# Relay.net
KiCad netlist of a schematic drawn in Altium Designer
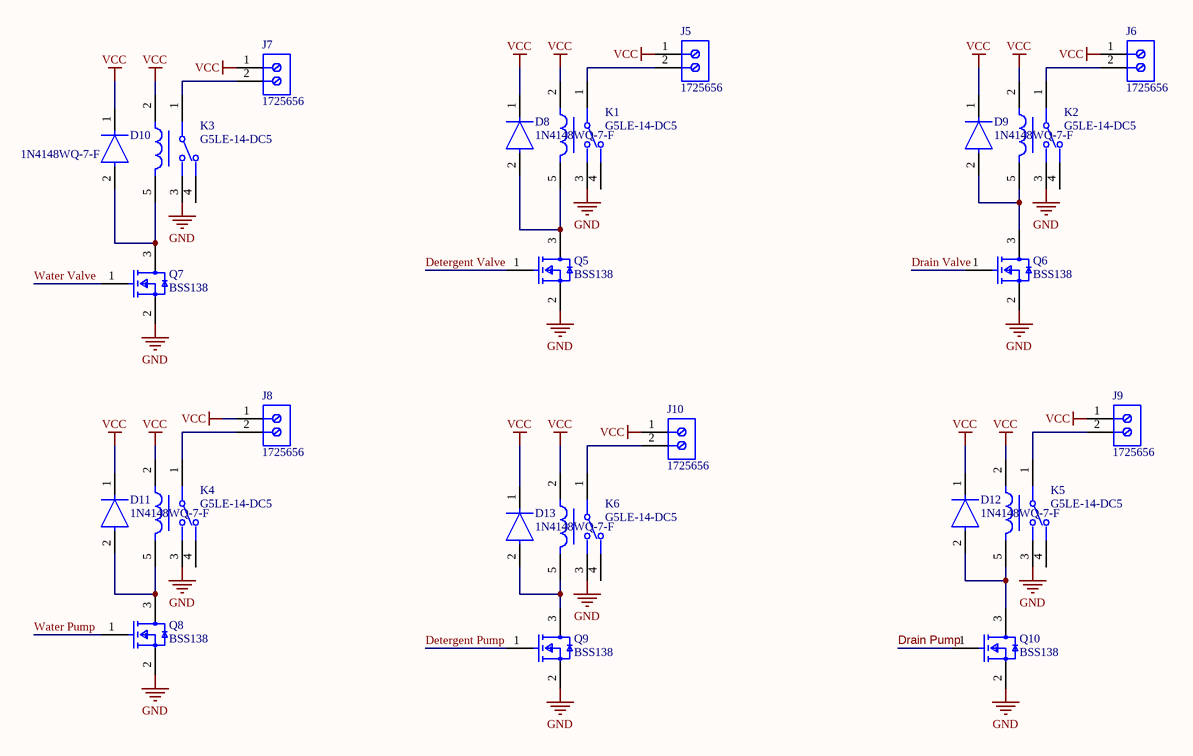
[diagram p0: Relay.SchDoc]

(export (version "E")
  (design (tool "Eeschema 10.0.6"))
  (components
    (comp (ref "D8")
      (value "1N4148WQ-7-F")
      (footprint "FP-SOD123-MFG")
      (description "DIODE GEN PURP 100V 300MA SOD123")
      (fields
        (field (name "MANUFACTURER") "Diodes Inc.")
        (field (name "OCTOPART") "https://octopart.com/1n4148wq-7-f-diodes+inc.-34965875")
      )
      (libsource (lib "Altium Content Vault") (part "d7152d700b627762746794eb795d46e"))
    )
    (comp (ref "D9")
      (value "1N4148WQ-7-F")
      (footprint "FP-SOD123-MFG")
      (description "DIODE GEN PURP 100V 300MA SOD123")
      (fields
        (field (name "MANUFACTURER") "Diodes Inc.")
        (field (name "OCTOPART") "https://octopart.com/1n4148wq-7-f-diodes+inc.-34965875")
      )
      (libsource (lib "Altium Content Vault") (part "d7152d700b627762746794eb795d46e"))
    )
    (comp (ref "D10")
      (value "1N4148WQ-7-F")
      (footprint "FP-SOD123-MFG")
      (description "DIODE GEN PURP 100V 300MA SOD123")
      (fields
        (field (name "MANUFACTURER") "Diodes Inc.")
        (field (name "OCTOPART") "https://octopart.com/1n4148wq-7-f-diodes+inc.-34965875")
      )
      (libsource (lib "Altium Content Vault") (part "d7152d700b627762746794eb795d46e"))
    )
    (comp (ref "D11")
      (value "1N4148WQ-7-F")
      (footprint "FP-SOD123-MFG")
      (description "DIODE GEN PURP 100V 300MA SOD123")
      (fields
        (field (name "MANUFACTURER") "Diodes Inc.")
        (field (name "OCTOPART") "https://octopart.com/1n4148wq-7-f-diodes+inc.-34965875")
      )
      (libsource (lib "Altium Content Vault") (part "d7152d700b627762746794eb795d46e"))
    )
    (comp (ref "D12")
      (value "1N4148WQ-7-F")
      (footprint "FP-SOD123-MFG")
      (description "DIODE GEN PURP 100V 300MA SOD123")
      (fields
        (field (name "MANUFACTURER") "Diodes Inc.")
        (field (name "OCTOPART") "https://octopart.com/1n4148wq-7-f-diodes+inc.-34965875")
      )
      (libsource (lib "Altium Content Vault") (part "d7152d700b627762746794eb795d46e"))
    )
    (comp (ref "D13")
      (value "1N4148WQ-7-F")
      (footprint "FP-SOD123-MFG")
      (description "DIODE GEN PURP 100V 300MA SOD123")
      (fields
        (field (name "MANUFACTURER") "Diodes Inc.")
        (field (name "OCTOPART") "https://octopart.com/1n4148wq-7-f-diodes+inc.-34965875")
      )
      (libsource (lib "Altium Content Vault") (part "d7152d700b627762746794eb795d46e"))
    )
    (comp (ref "J5")
      (value "1725656")
      (footprint "PHOE-1725656-2")
      (description "Male Header, Pitch 2.54 mm, 1 x 2 Position, Height 9 mm, Tail Length 3.5 mm")
      (fields (field (name "MANUFACTURER") "Phoenix Contact"))
      (libsource (lib "Altium Content Vault") (part "CN-1P-F-TB2"))
    )
    (comp (ref "J6")
      (value "1725656")
      (footprint "PHOE-1725656-2")
      (description "Male Header, Pitch 2.54 mm, 1 x 2 Position, Height 9 mm, Tail Length 3.5 mm")
      (fields (field (name "MANUFACTURER") "Phoenix Contact"))
      (libsource (lib "Altium Content Vault") (part "CN-1P-F-TB2"))
    )
    (comp (ref "J7")
      (value "1725656")
      (footprint "PHOE-1725656-2")
      (description "Male Header, Pitch 2.54 mm, 1 x 2 Position, Height 9 mm, Tail Length 3.5 mm")
      (fields (field (name "MANUFACTURER") "Phoenix Contact"))
      (libsource (lib "Altium Content Vault") (part "CN-1P-F-TB2"))
    )
    (comp (ref "J8")
      (value "1725656")
      (footprint "PHOE-1725656-2")
      (description "Male Header, Pitch 2.54 mm, 1 x 2 Position, Height 9 mm, Tail Length 3.5 mm")
      (fields (field (name "MANUFACTURER") "Phoenix Contact"))
      (libsource (lib "Altium Content Vault") (part "CN-1P-F-TB2"))
    )
    (comp (ref "J9")
      (value "1725656")
      (footprint "PHOE-1725656-2")
      (description "Male Header, Pitch 2.54 mm, 1 x 2 Position, Height 9 mm, Tail Length 3.5 mm")
      (fields (field (name "MANUFACTURER") "Phoenix Contact"))
      (libsource (lib "Altium Content Vault") (part "CN-1P-F-TB2"))
    )
    (comp (ref "J10")
      (value "1725656")
      (footprint "PHOE-1725656-2")
      (description "Male Header, Pitch 2.54 mm, 1 x 2 Position, Height 9 mm, Tail Length 3.5 mm")
      (fields (field (name "MANUFACTURER") "Phoenix Contact"))
      (libsource (lib "Altium Content Vault") (part "CN-1P-F-TB2"))
    )
    (comp (ref "K1")
      (value "G5LE-14-DC5")
      (footprint "FP-G5LE-14-DC5-MFG")
      (description "RELAY GEN PURPOSE SPDT 10A 5V")
      (fields
        (field (name "OCTOPART") "https://octopart.com/g5le-14-dc5-omron-28829")
        (field (name "MANUFACTURER") "Omron")
      )
      (libsource (lib "Altium Content Vault") (part "c03b8d08e5d02e70a6880f365e34168"))
    )
    (comp (ref "K2")
      (value "G5LE-14-DC5")
      (footprint "FP-G5LE-14-DC5-MFG")
      (description "RELAY GEN PURPOSE SPDT 10A 5V")
      (fields
        (field (name "OCTOPART") "https://octopart.com/g5le-14-dc5-omron-28829")
        (field (name "MANUFACTURER") "Omron")
      )
      (libsource (lib "Altium Content Vault") (part "c03b8d08e5d02e70a6880f365e34168"))
    )
    (comp (ref "K3")
      (value "G5LE-14-DC5")
      (footprint "FP-G5LE-14-DC5-MFG")
      (description "RELAY GEN PURPOSE SPDT 10A 5V")
      (fields
        (field (name "OCTOPART") "https://octopart.com/g5le-14-dc5-omron-28829")
        (field (name "MANUFACTURER") "Omron")
      )
      (libsource (lib "Altium Content Vault") (part "c03b8d08e5d02e70a6880f365e34168"))
    )
    (comp (ref "K4")
      (value "G5LE-14-DC5")
      (footprint "FP-G5LE-14-DC5-MFG")
      (description "RELAY GEN PURPOSE SPDT 10A 5V")
      (fields
        (field (name "OCTOPART") "https://octopart.com/g5le-14-dc5-omron-28829")
        (field (name "MANUFACTURER") "Omron")
      )
      (libsource (lib "Altium Content Vault") (part "c03b8d08e5d02e70a6880f365e34168"))
    )
    (comp (ref "K5")
      (value "G5LE-14-DC5")
      (footprint "FP-G5LE-14-DC5-MFG")
      (description "RELAY GEN PURPOSE SPDT 10A 5V")
      (fields
        (field (name "OCTOPART") "https://octopart.com/g5le-14-dc5-omron-28829")
        (field (name "MANUFACTURER") "Omron")
      )
      (libsource (lib "Altium Content Vault") (part "c03b8d08e5d02e70a6880f365e34168"))
    )
    (comp (ref "K6")
      (value "G5LE-14-DC5")
      (footprint "FP-G5LE-14-DC5-MFG")
      (description "RELAY GEN PURPOSE SPDT 10A 5V")
      (fields
        (field (name "OCTOPART") "https://octopart.com/g5le-14-dc5-omron-28829")
        (field (name "MANUFACTURER") "Omron")
      )
      (libsource (lib "Altium Content Vault") (part "c03b8d08e5d02e70a6880f365e34168"))
    )
    (comp (ref "Q5")
      (value "BSS138")
      (footprint "FP-318-08-IPC_A")
      (description "MOSFET N-CH 50V 220MA SOT-23")
      (libsource (lib "Altium Content Vault") (part "3b9c635fedb024a5347a57b145af9cc"))
    )
    (comp (ref "Q6")
      (value "BSS138")
      (footprint "FP-318-08-IPC_A")
      (description "MOSFET N-CH 50V 220MA SOT-23")
      (libsource (lib "Altium Content Vault") (part "3b9c635fedb024a5347a57b145af9cc"))
    )
    (comp (ref "Q7")
      (value "BSS138")
      (footprint "FP-318-08-IPC_A")
      (description "MOSFET N-CH 50V 220MA SOT-23")
      (libsource (lib "Altium Content Vault") (part "3b9c635fedb024a5347a57b145af9cc"))
    )
    (comp (ref "Q8")
      (value "BSS138")
      (footprint "FP-318-08-IPC_A")
      (description "MOSFET N-CH 50V 220MA SOT-23")
      (libsource (lib "Altium Content Vault") (part "3b9c635fedb024a5347a57b145af9cc"))
    )
    (comp (ref "Q9")
      (value "BSS138")
      (footprint "FP-318-08-IPC_A")
      (description "MOSFET N-CH 50V 220MA SOT-23")
      (libsource (lib "Altium Content Vault") (part "3b9c635fedb024a5347a57b145af9cc"))
    )
    (comp (ref "Q10")
      (value "BSS138")
      (footprint "FP-318-08-IPC_A")
      (description "MOSFET N-CH 50V 220MA SOT-23")
      (libsource (lib "Altium Content Vault") (part "3b9c635fedb024a5347a57b145af9cc"))
    )
  )
  (nets
    (net (code "1") (name "/Detergent Pump") (class "Default")
      (node (ref "Q9") (pin "1") (pinfunction "G_1") (pintype "passive"))
    )
    (net (code "2") (name "/Detergent Valve") (class "Default")
      (node (ref "Q5") (pin "1") (pinfunction "G_1") (pintype "passive"))
    )
    (net (code "3") (name "/Drain Pump") (class "Default")
      (node (ref "Q10") (pin "1") (pinfunction "G_1") (pintype "passive"))
    )
    (net (code "4") (name "/Drain Valve") (class "Default")
      (node (ref "Q6") (pin "1") (pinfunction "G_1") (pintype "passive"))
    )
    (net (code "5") (name "/Water Pump") (class "Default")
      (node (ref "Q8") (pin "1") (pinfunction "G_1") (pintype "passive"))
    )
    (net (code "6") (name "/Water Valve") (class "Default")
      (node (ref "Q7") (pin "1") (pinfunction "G_1") (pintype "passive"))
    )
    (net (code "7") (name "GND") (class "Default")
      (node (ref "K1") (pin "3") (pinfunction "3_3") (pintype "passive"))
      (node (ref "K2") (pin "3") (pinfunction "3_3") (pintype "passive"))
      (node (ref "K3") (pin "3") (pinfunction "3_3") (pintype "passive"))
      (node (ref "K4") (pin "3") (pinfunction "3_3") (pintype "passive"))
      (node (ref "K5") (pin "3") (pinfunction "3_3") (pintype "passive"))
      (node (ref "K6") (pin "3") (pinfunction "3_3") (pintype "passive"))
      (node (ref "Q10") (pin "2") (pinfunction "S_2") (pintype "passive"))
      (node (ref "Q5") (pin "2") (pinfunction "S_2") (pintype "passive"))
      (node (ref "Q6") (pin "2") (pinfunction "S_2") (pintype "passive"))
      (node (ref "Q7") (pin "2") (pinfunction "S_2") (pintype "passive"))
      (node (ref "Q8") (pin "2") (pinfunction "S_2") (pintype "passive"))
      (node (ref "Q9") (pin "2") (pinfunction "S_2") (pintype "passive"))
    )
    (net (code "8") (name "Net-(D8-A)") (class "Default")
      (node (ref "D8") (pin "2") (pinfunction "A_2") (pintype "passive"))
      (node (ref "K1") (pin "5") (pinfunction "5_5") (pintype "passive"))
      (node (ref "Q5") (pin "3") (pinfunction "D_3") (pintype "passive"))
    )
    (net (code "9") (name "Net-(D9-A)") (class "Default")
      (node (ref "D9") (pin "2") (pinfunction "A_2") (pintype "passive"))
      (node (ref "K2") (pin "5") (pinfunction "5_5") (pintype "passive"))
      (node (ref "Q6") (pin "3") (pinfunction "D_3") (pintype "passive"))
    )
    (net (code "10") (name "Net-(D10-A)") (class "Default")
      (node (ref "D10") (pin "2") (pinfunction "A_2") (pintype "passive"))
      (node (ref "K3") (pin "5") (pinfunction "5_5") (pintype "passive"))
      (node (ref "Q7") (pin "3") (pinfunction "D_3") (pintype "passive"))
    )
    (net (code "11") (name "Net-(D11-A)") (class "Default")
      (node (ref "D11") (pin "2") (pinfunction "A_2") (pintype "passive"))
      (node (ref "K4") (pin "5") (pinfunction "5_5") (pintype "passive"))
      (node (ref "Q8") (pin "3") (pinfunction "D_3") (pintype "passive"))
    )
    (net (code "12") (name "Net-(D12-A)") (class "Default")
      (node (ref "D12") (pin "2") (pinfunction "A_2") (pintype "passive"))
      (node (ref "K5") (pin "5") (pinfunction "5_5") (pintype "passive"))
      (node (ref "Q10") (pin "3") (pinfunction "D_3") (pintype "passive"))
    )
    (net (code "13") (name "Net-(D13-A)") (class "Default")
      (node (ref "D13") (pin "2") (pinfunction "A_2") (pintype "passive"))
      (node (ref "K6") (pin "5") (pinfunction "5_5") (pintype "passive"))
      (node (ref "Q9") (pin "3") (pinfunction "D_3") (pintype "passive"))
    )
    (net (code "14") (name "Net-(J5-Pad2)") (class "Default")
      (node (ref "J5") (pin "2") (pinfunction "2_2") (pintype "passive"))
      (node (ref "K1") (pin "1") (pinfunction "1_1") (pintype "passive"))
    )
    (net (code "15") (name "Net-(J6-Pad2)") (class "Default")
      (node (ref "J6") (pin "2") (pinfunction "2_2") (pintype "passive"))
      (node (ref "K2") (pin "1") (pinfunction "1_1") (pintype "passive"))
    )
    (net (code "16") (name "Net-(J7-Pad2)") (class "Default")
      (node (ref "J7") (pin "2") (pinfunction "2_2") (pintype "passive"))
      (node (ref "K3") (pin "1") (pinfunction "1_1") (pintype "passive"))
    )
    (net (code "17") (name "Net-(J8-Pad2)") (class "Default")
      (node (ref "J8") (pin "2") (pinfunction "2_2") (pintype "passive"))
      (node (ref "K4") (pin "1") (pinfunction "1_1") (pintype "passive"))
    )
    (net (code "18") (name "Net-(J9-Pad2)") (class "Default")
      (node (ref "J9") (pin "2") (pinfunction "2_2") (pintype "passive"))
      (node (ref "K5") (pin "1") (pinfunction "1_1") (pintype "passive"))
    )
    (net (code "19") (name "Net-(J10-Pad2)") (class "Default")
      (node (ref "J10") (pin "2") (pinfunction "2_2") (pintype "passive"))
      (node (ref "K6") (pin "1") (pinfunction "1_1") (pintype "passive"))
    )
    (net (code "20") (name "VCC") (class "Default")
      (node (ref "D10") (pin "1") (pinfunction "C_1") (pintype "passive"))
      (node (ref "D11") (pin "1") (pinfunction "C_1") (pintype "passive"))
      (node (ref "D12") (pin "1") (pinfunction "C_1") (pintype "passive"))
      (node (ref "D13") (pin "1") (pinfunction "C_1") (pintype "passive"))
      (node (ref "D8") (pin "1") (pinfunction "C_1") (pintype "passive"))
      (node (ref "D9") (pin "1") (pinfunction "C_1") (pintype "passive"))
      (node (ref "J10") (pin "1") (pinfunction "1_1") (pintype "passive"))
      (node (ref "J5") (pin "1") (pinfunction "1_1") (pintype "passive"))
      (node (ref "J6") (pin "1") (pinfunction "1_1") (pintype "passive"))
      (node (ref "J7") (pin "1") (pinfunction "1_1") (pintype "passive"))
      (node (ref "J8") (pin "1") (pinfunction "1_1") (pintype "passive"))
      (node (ref "J9") (pin "1") (pinfunction "1_1") (pintype "passive"))
      (node (ref "K1") (pin "2") (pinfunction "2_2") (pintype "passive"))
      (node (ref "K2") (pin "2") (pinfunction "2_2") (pintype "passive"))
      (node (ref "K3") (pin "2") (pinfunction "2_2") (pintype "passive"))
      (node (ref "K4") (pin "2") (pinfunction "2_2") (pintype "passive"))
      (node (ref "K5") (pin "2") (pinfunction "2_2") (pintype "passive"))
      (node (ref "K6") (pin "2") (pinfunction "2_2") (pintype "passive"))
    )
    (net (code "21") (name "unconnected-(K1-Pad4)") (class "Default")
      (node (ref "K1") (pin "4") (pinfunction "4_4") (pintype "passive"))
    )
    (net (code "22") (name "unconnected-(K2-Pad4)") (class "Default")
      (node (ref "K2") (pin "4") (pinfunction "4_4") (pintype "passive"))
    )
    (net (code "23") (name "unconnected-(K3-Pad4)") (class "Default")
      (node (ref "K3") (pin "4") (pinfunction "4_4") (pintype "passive"))
    )
    (net (code "24") (name "unconnected-(K4-Pad4)") (class "Default")
      (node (ref "K4") (pin "4") (pinfunction "4_4") (pintype "passive"))
    )
    (net (code "25") (name "unconnected-(K5-Pad4)") (class "Default")
      (node (ref "K5") (pin "4") (pinfunction "4_4") (pintype "passive"))
    )
    (net (code "26") (name "unconnected-(K6-Pad4)") (class "Default")
      (node (ref "K6") (pin "4") (pinfunction "4_4") (pintype "passive"))
    )
  )
)
